# iprobe.net
KiCad netlist of a schematic drawn in EAGLE
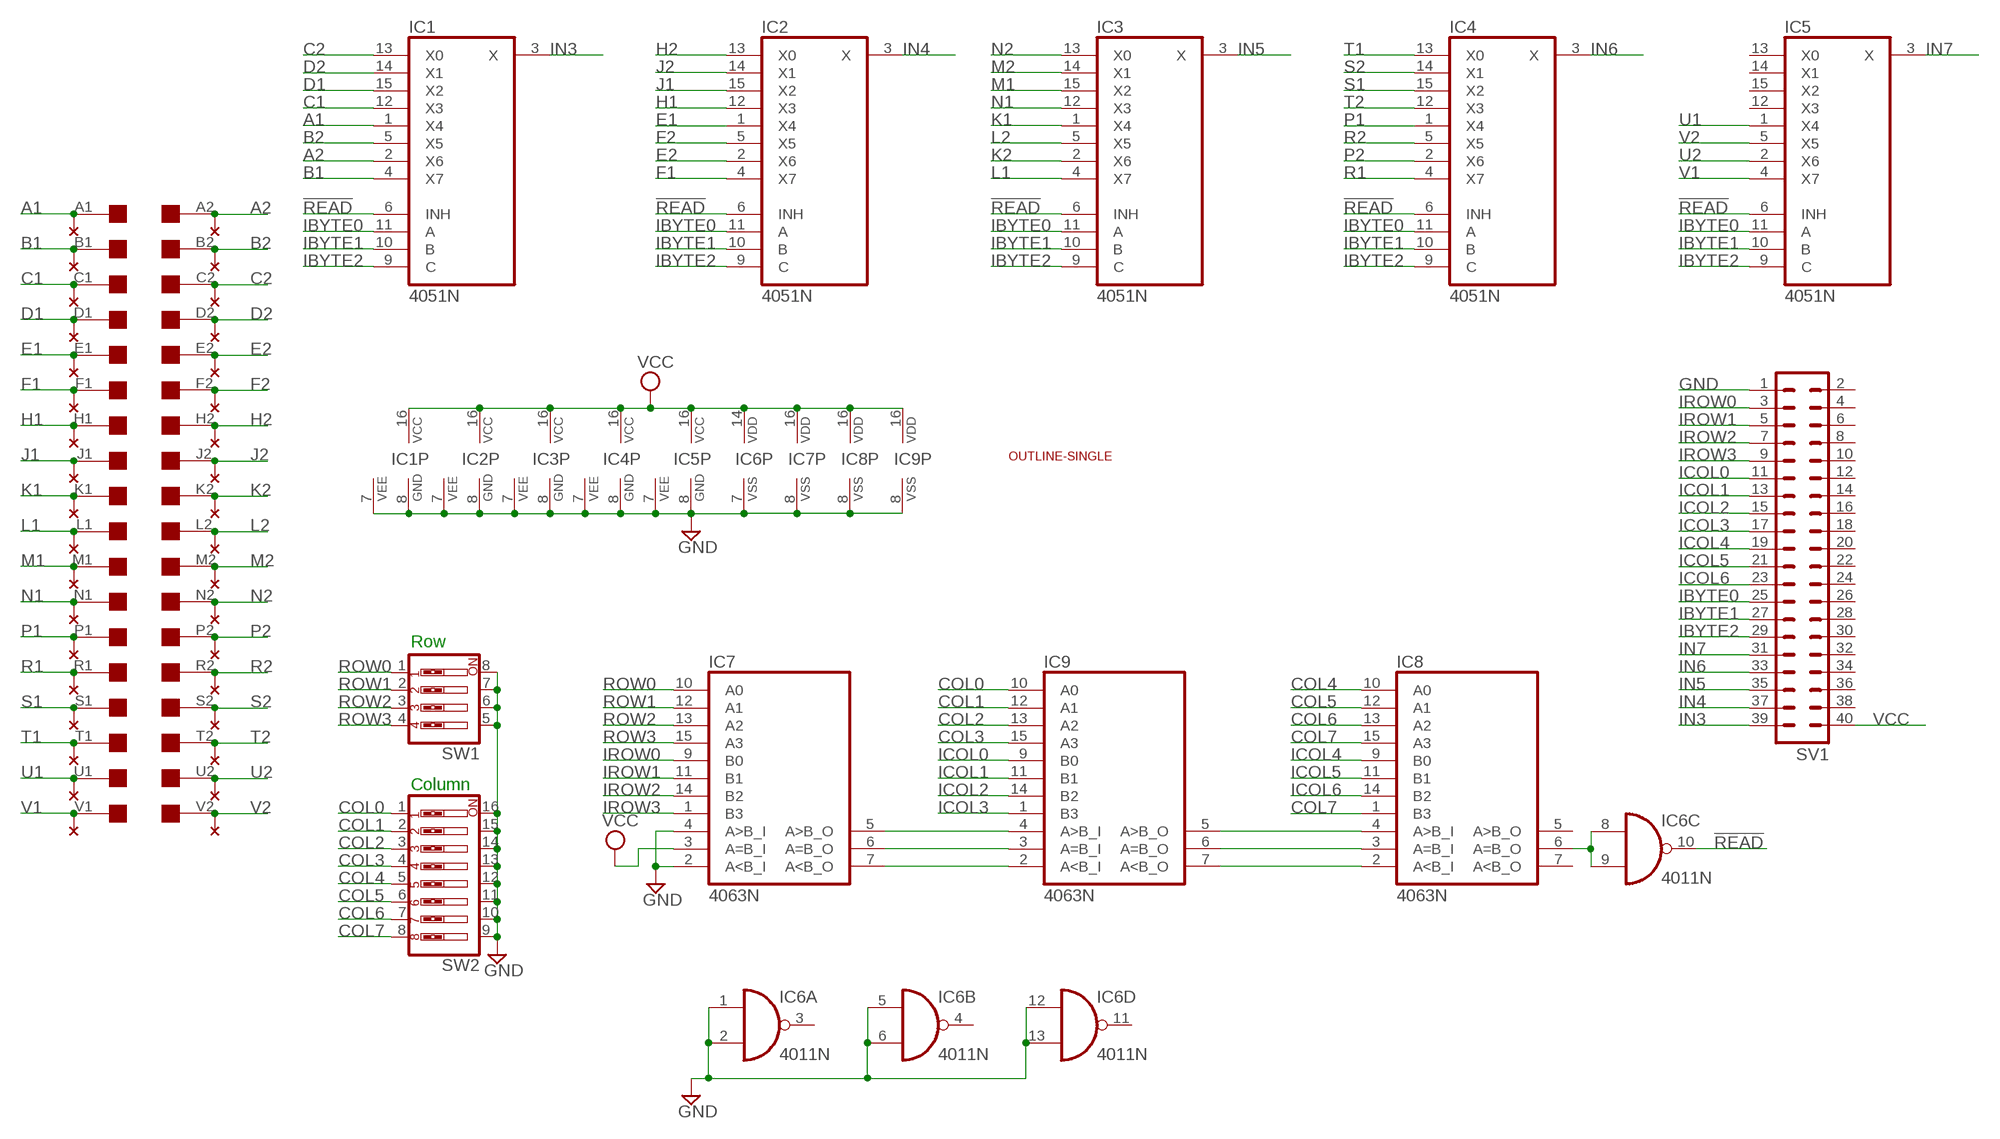
[diagram p0: schematic, sheet 1]

(export (version "E")
  (design (tool "Eeschema 10.0.6"))
  (components
    (comp (ref "EDGE1")
      (value "EDGE-2CONNECTOR")
      (footprint "eagle-import:EDGE-CON2")
      (libsource (lib "eagle-import") (part "EDGE-2CONNECTOR"))
    )
    (comp (ref "IC1")
      (value "4051N")
      (footprint "eagle-import:DIL16")
      (libsource (lib "eagle-import") (part "4051N"))
    )
    (comp (ref "IC2")
      (value "4051N")
      (footprint "eagle-import:DIL16")
      (libsource (lib "eagle-import") (part "4051N"))
    )
    (comp (ref "IC3")
      (value "4051N")
      (footprint "eagle-import:DIL16")
      (libsource (lib "eagle-import") (part "4051N"))
    )
    (comp (ref "IC4")
      (value "4051N")
      (footprint "eagle-import:DIL16")
      (libsource (lib "eagle-import") (part "4051N"))
    )
    (comp (ref "IC5")
      (value "4051N")
      (footprint "eagle-import:DIL16")
      (libsource (lib "eagle-import") (part "4051N"))
    )
    (comp (ref "IC6")
      (value "4011N")
      (footprint "eagle-import:DIL14")
      (libsource (lib "eagle-import") (part "4011N"))
    )
    (comp (ref "IC7")
      (value "4063N")
      (footprint "eagle-import:DIL16")
      (libsource (lib "eagle-import") (part "4063N"))
    )
    (comp (ref "IC8")
      (value "4063N")
      (footprint "eagle-import:DIL16")
      (libsource (lib "eagle-import") (part "4063N"))
    )
    (comp (ref "IC9")
      (value "4063N")
      (footprint "eagle-import:DIL16")
      (libsource (lib "eagle-import") (part "4063N"))
    )
    (comp (ref "SV1")
      (value "MA20-2")
      (footprint "eagle-import:MA20-2")
      (libsource (lib "eagle-import") (part "MA20-2"))
    )
    (comp (ref "SW1")
      (value "SW_DIP-4")
      (footprint "eagle-import:EDG-04")
      (libsource (lib "eagle-import") (part "SW_DIP-4"))
    )
    (comp (ref "SW2")
      (value "SW_DIP-8")
      (footprint "eagle-import:EDG-08")
      (libsource (lib "eagle-import") (part "SW_DIP-8"))
    )
    (comp (ref "U$2")
      (value "THRU-HOLE2")
      (footprint "eagle-import:THRU-HOLEB")
      (libsource (lib "eagle-import") (part "THRU-HOLE2"))
    )
    (comp (ref "U$3")
      (value "OUTLINE-SINGLE")
      (footprint "eagle-import:SINGLE")
      (libsource (lib "eagle-import") (part "OUTLINE-SINGLE"))
    )
  )
  (nets
    (net (code "1") (name "/A1") (class "Default")
      (node (ref "EDGE1") (pin "A1") (pinfunction "1_A1") (pintype "bidirectional"))
      (node (ref "IC1") (pin "1") (pinfunction "X4_1") (pintype "bidirectional"))
      (node (ref "U$2") (pin "A1") (pinfunction "P$1_A1") (pintype "passive"))
    )
    (net (code "2") (name "/A2") (class "Default")
      (node (ref "EDGE1") (pin "A2") (pinfunction "1_A2") (pintype "bidirectional"))
      (node (ref "IC1") (pin "2") (pinfunction "X6_2") (pintype "bidirectional"))
      (node (ref "U$2") (pin "A2") (pinfunction "P$1_A2") (pintype "passive"))
    )
    (net (code "3") (name "/B1") (class "Default")
      (node (ref "EDGE1") (pin "B1") (pinfunction "1_B1") (pintype "bidirectional"))
      (node (ref "IC1") (pin "4") (pinfunction "X7_4") (pintype "bidirectional"))
      (node (ref "U$2") (pin "B1") (pinfunction "P$1_B1") (pintype "passive"))
    )
    (net (code "4") (name "/B2") (class "Default")
      (node (ref "EDGE1") (pin "B2") (pinfunction "1_B2") (pintype "bidirectional"))
      (node (ref "IC1") (pin "5") (pinfunction "X5_5") (pintype "bidirectional"))
      (node (ref "U$2") (pin "B2") (pinfunction "P$1_B2") (pintype "passive"))
    )
    (net (code "5") (name "/C1") (class "Default")
      (node (ref "EDGE1") (pin "C1") (pinfunction "1_C1") (pintype "bidirectional"))
      (node (ref "IC1") (pin "12") (pinfunction "X3_12") (pintype "bidirectional"))
      (node (ref "U$2") (pin "C1") (pinfunction "P$1_C1") (pintype "passive"))
    )
    (net (code "6") (name "/C2") (class "Default")
      (node (ref "EDGE1") (pin "C2") (pinfunction "1_C2") (pintype "bidirectional"))
      (node (ref "IC1") (pin "13") (pinfunction "X0_13") (pintype "bidirectional"))
      (node (ref "U$2") (pin "C2") (pinfunction "P$1_C2") (pintype "passive"))
    )
    (net (code "7") (name "/COL0") (class "Default")
      (node (ref "IC9") (pin "10") (pinfunction "A0_10") (pintype "input"))
      (node (ref "SW2") (pin "1") (pinfunction "1_1") (pintype "passive"))
    )
    (net (code "8") (name "/COL1") (class "Default")
      (node (ref "IC9") (pin "12") (pinfunction "A1_12") (pintype "input"))
      (node (ref "SW2") (pin "2") (pinfunction "2_2") (pintype "passive"))
    )
    (net (code "9") (name "/COL2") (class "Default")
      (node (ref "IC9") (pin "13") (pinfunction "A2_13") (pintype "input"))
      (node (ref "SW2") (pin "3") (pinfunction "3_3") (pintype "passive"))
    )
    (net (code "10") (name "/COL3") (class "Default")
      (node (ref "IC9") (pin "15") (pinfunction "A3_15") (pintype "input"))
      (node (ref "SW2") (pin "4") (pinfunction "4_4") (pintype "passive"))
    )
    (net (code "11") (name "/COL4") (class "Default")
      (node (ref "IC8") (pin "10") (pinfunction "A0_10") (pintype "input"))
      (node (ref "SW2") (pin "5") (pinfunction "5_5") (pintype "passive"))
    )
    (net (code "12") (name "/COL5") (class "Default")
      (node (ref "IC8") (pin "12") (pinfunction "A1_12") (pintype "input"))
      (node (ref "SW2") (pin "6") (pinfunction "6_6") (pintype "passive"))
    )
    (net (code "13") (name "/COL6") (class "Default")
      (node (ref "IC8") (pin "13") (pinfunction "A2_13") (pintype "input"))
      (node (ref "SW2") (pin "7") (pinfunction "7_7") (pintype "passive"))
    )
    (net (code "14") (name "/COL7") (class "Default")
      (node (ref "IC8") (pin "1") (pinfunction "B3_1") (pintype "input"))
      (node (ref "IC8") (pin "15") (pinfunction "A3_15") (pintype "input"))
      (node (ref "SW2") (pin "8") (pinfunction "8_8") (pintype "passive"))
    )
    (net (code "15") (name "/D1") (class "Default")
      (node (ref "EDGE1") (pin "D1") (pinfunction "1_D1") (pintype "bidirectional"))
      (node (ref "IC1") (pin "15") (pinfunction "X2_15") (pintype "bidirectional"))
      (node (ref "U$2") (pin "D1") (pinfunction "P$1_D1") (pintype "passive"))
    )
    (net (code "16") (name "/D2") (class "Default")
      (node (ref "EDGE1") (pin "D2") (pinfunction "1_D2") (pintype "bidirectional"))
      (node (ref "IC1") (pin "14") (pinfunction "X1_14") (pintype "bidirectional"))
      (node (ref "U$2") (pin "D2") (pinfunction "P$1_D2") (pintype "passive"))
    )
    (net (code "17") (name "/E1") (class "Default")
      (node (ref "EDGE1") (pin "E1") (pinfunction "1_E1") (pintype "bidirectional"))
      (node (ref "IC2") (pin "1") (pinfunction "X4_1") (pintype "bidirectional"))
      (node (ref "U$2") (pin "E1") (pinfunction "P$1_E1") (pintype "passive"))
    )
    (net (code "18") (name "/E2") (class "Default")
      (node (ref "EDGE1") (pin "E2") (pinfunction "1_E2") (pintype "bidirectional"))
      (node (ref "IC2") (pin "2") (pinfunction "X6_2") (pintype "bidirectional"))
      (node (ref "U$2") (pin "E2") (pinfunction "P$1_E2") (pintype "passive"))
    )
    (net (code "19") (name "/F1") (class "Default")
      (node (ref "EDGE1") (pin "F1") (pinfunction "1_F1") (pintype "bidirectional"))
      (node (ref "IC2") (pin "4") (pinfunction "X7_4") (pintype "bidirectional"))
      (node (ref "U$2") (pin "F1") (pinfunction "P$1_F1") (pintype "passive"))
    )
    (net (code "20") (name "/F2") (class "Default")
      (node (ref "EDGE1") (pin "F2") (pinfunction "1_F2") (pintype "bidirectional"))
      (node (ref "IC2") (pin "5") (pinfunction "X5_5") (pintype "bidirectional"))
      (node (ref "U$2") (pin "F2") (pinfunction "P$1_F2") (pintype "passive"))
    )
    (net (code "21") (name "/H1") (class "Default")
      (node (ref "EDGE1") (pin "H1") (pinfunction "1_H1") (pintype "bidirectional"))
      (node (ref "IC2") (pin "12") (pinfunction "X3_12") (pintype "bidirectional"))
      (node (ref "U$2") (pin "H1") (pinfunction "P$1_H1") (pintype "passive"))
    )
    (net (code "22") (name "/H2") (class "Default")
      (node (ref "EDGE1") (pin "H2") (pinfunction "1_H2") (pintype "bidirectional"))
      (node (ref "IC2") (pin "13") (pinfunction "X0_13") (pintype "bidirectional"))
      (node (ref "U$2") (pin "H2") (pinfunction "P$1_H2") (pintype "passive"))
    )
    (net (code "23") (name "/IBYTE0") (class "Default")
      (node (ref "IC1") (pin "11") (pinfunction "A_11") (pintype "input"))
      (node (ref "IC2") (pin "11") (pinfunction "A_11") (pintype "input"))
      (node (ref "IC3") (pin "11") (pinfunction "A_11") (pintype "input"))
      (node (ref "IC4") (pin "11") (pinfunction "A_11") (pintype "input"))
      (node (ref "IC5") (pin "11") (pinfunction "A_11") (pintype "input"))
      (node (ref "SV1") (pin "25") (pinfunction "25_25") (pintype "passive"))
    )
    (net (code "24") (name "/IBYTE1") (class "Default")
      (node (ref "IC1") (pin "10") (pinfunction "B_10") (pintype "input"))
      (node (ref "IC2") (pin "10") (pinfunction "B_10") (pintype "input"))
      (node (ref "IC3") (pin "10") (pinfunction "B_10") (pintype "input"))
      (node (ref "IC4") (pin "10") (pinfunction "B_10") (pintype "input"))
      (node (ref "IC5") (pin "10") (pinfunction "B_10") (pintype "input"))
      (node (ref "SV1") (pin "27") (pinfunction "27_27") (pintype "passive"))
    )
    (net (code "25") (name "/IBYTE2") (class "Default")
      (node (ref "IC1") (pin "9") (pinfunction "C_9") (pintype "input"))
      (node (ref "IC2") (pin "9") (pinfunction "C_9") (pintype "input"))
      (node (ref "IC3") (pin "9") (pinfunction "C_9") (pintype "input"))
      (node (ref "IC4") (pin "9") (pinfunction "C_9") (pintype "input"))
      (node (ref "IC5") (pin "9") (pinfunction "C_9") (pintype "input"))
      (node (ref "SV1") (pin "29") (pinfunction "29_29") (pintype "passive"))
    )
    (net (code "26") (name "/ICOL0") (class "Default")
      (node (ref "IC9") (pin "9") (pinfunction "B0_9") (pintype "input"))
      (node (ref "SV1") (pin "11") (pinfunction "11_11") (pintype "passive"))
    )
    (net (code "27") (name "/ICOL1") (class "Default")
      (node (ref "IC9") (pin "11") (pinfunction "B1_11") (pintype "input"))
      (node (ref "SV1") (pin "13") (pinfunction "13_13") (pintype "passive"))
    )
    (net (code "28") (name "/ICOL2") (class "Default")
      (node (ref "IC9") (pin "14") (pinfunction "B2_14") (pintype "input"))
      (node (ref "SV1") (pin "15") (pinfunction "15_15") (pintype "passive"))
    )
    (net (code "29") (name "/ICOL3") (class "Default")
      (node (ref "IC9") (pin "1") (pinfunction "B3_1") (pintype "input"))
      (node (ref "SV1") (pin "17") (pinfunction "17_17") (pintype "passive"))
    )
    (net (code "30") (name "/ICOL4") (class "Default")
      (node (ref "IC8") (pin "9") (pinfunction "B0_9") (pintype "input"))
      (node (ref "SV1") (pin "19") (pinfunction "19_19") (pintype "passive"))
    )
    (net (code "31") (name "/ICOL5") (class "Default")
      (node (ref "IC8") (pin "11") (pinfunction "B1_11") (pintype "input"))
      (node (ref "SV1") (pin "21") (pinfunction "21_21") (pintype "passive"))
    )
    (net (code "32") (name "/ICOL6") (class "Default")
      (node (ref "IC8") (pin "14") (pinfunction "B2_14") (pintype "input"))
      (node (ref "SV1") (pin "23") (pinfunction "23_23") (pintype "passive"))
    )
    (net (code "33") (name "/IN3") (class "Default")
      (node (ref "IC1") (pin "3") (pinfunction "X_3") (pintype "bidirectional"))
      (node (ref "SV1") (pin "39") (pinfunction "39_39") (pintype "passive"))
    )
    (net (code "34") (name "/IN4") (class "Default")
      (node (ref "IC2") (pin "3") (pinfunction "X_3") (pintype "bidirectional"))
      (node (ref "SV1") (pin "37") (pinfunction "37_37") (pintype "passive"))
    )
    (net (code "35") (name "/IN5") (class "Default")
      (node (ref "IC3") (pin "3") (pinfunction "X_3") (pintype "bidirectional"))
      (node (ref "SV1") (pin "35") (pinfunction "35_35") (pintype "passive"))
    )
    (net (code "36") (name "/IN6") (class "Default")
      (node (ref "IC4") (pin "3") (pinfunction "X_3") (pintype "bidirectional"))
      (node (ref "SV1") (pin "33") (pinfunction "33_33") (pintype "passive"))
    )
    (net (code "37") (name "/IN7") (class "Default")
      (node (ref "IC5") (pin "3") (pinfunction "X_3") (pintype "bidirectional"))
      (node (ref "SV1") (pin "31") (pinfunction "31_31") (pintype "passive"))
    )
    (net (code "38") (name "/IROW0") (class "Default")
      (node (ref "IC7") (pin "9") (pinfunction "B0_9") (pintype "input"))
      (node (ref "SV1") (pin "3") (pinfunction "3_3") (pintype "passive"))
    )
    (net (code "39") (name "/IROW1") (class "Default")
      (node (ref "IC7") (pin "11") (pinfunction "B1_11") (pintype "input"))
      (node (ref "SV1") (pin "5") (pinfunction "5_5") (pintype "passive"))
    )
    (net (code "40") (name "/IROW2") (class "Default")
      (node (ref "IC7") (pin "14") (pinfunction "B2_14") (pintype "input"))
      (node (ref "SV1") (pin "7") (pinfunction "7_7") (pintype "passive"))
    )
    (net (code "41") (name "/IROW3") (class "Default")
      (node (ref "IC7") (pin "1") (pinfunction "B3_1") (pintype "input"))
      (node (ref "SV1") (pin "9") (pinfunction "9_9") (pintype "passive"))
    )
    (net (code "42") (name "/J1") (class "Default")
      (node (ref "EDGE1") (pin "J1") (pinfunction "1_J1") (pintype "bidirectional"))
      (node (ref "IC2") (pin "15") (pinfunction "X2_15") (pintype "bidirectional"))
      (node (ref "U$2") (pin "J1") (pinfunction "P$1_J1") (pintype "passive"))
    )
    (net (code "43") (name "/J2") (class "Default")
      (node (ref "EDGE1") (pin "J2") (pinfunction "1_J2") (pintype "bidirectional"))
      (node (ref "IC2") (pin "14") (pinfunction "X1_14") (pintype "bidirectional"))
      (node (ref "U$2") (pin "J2") (pinfunction "P$1_J2") (pintype "passive"))
    )
    (net (code "44") (name "/K1") (class "Default")
      (node (ref "EDGE1") (pin "K1") (pinfunction "1_K1") (pintype "bidirectional"))
      (node (ref "IC3") (pin "1") (pinfunction "X4_1") (pintype "bidirectional"))
      (node (ref "U$2") (pin "K1") (pinfunction "P$1_K1") (pintype "passive"))
    )
    (net (code "45") (name "/K2") (class "Default")
      (node (ref "EDGE1") (pin "K2") (pinfunction "1_K2") (pintype "bidirectional"))
      (node (ref "IC3") (pin "2") (pinfunction "X6_2") (pintype "bidirectional"))
      (node (ref "U$2") (pin "K2") (pinfunction "P$1_K2") (pintype "passive"))
    )
    (net (code "46") (name "/L1") (class "Default")
      (node (ref "EDGE1") (pin "L1") (pinfunction "1_L1") (pintype "bidirectional"))
      (node (ref "IC3") (pin "4") (pinfunction "X7_4") (pintype "bidirectional"))
      (node (ref "U$2") (pin "L1") (pinfunction "P$1_L1") (pintype "passive"))
    )
    (net (code "47") (name "/L2") (class "Default")
      (node (ref "EDGE1") (pin "L2") (pinfunction "1_L2") (pintype "bidirectional"))
      (node (ref "IC3") (pin "5") (pinfunction "X5_5") (pintype "bidirectional"))
      (node (ref "U$2") (pin "L2") (pinfunction "P$1_L2") (pintype "passive"))
    )
    (net (code "48") (name "/M1") (class "Default")
      (node (ref "EDGE1") (pin "M1") (pinfunction "1_M1") (pintype "bidirectional"))
      (node (ref "IC3") (pin "15") (pinfunction "X2_15") (pintype "bidirectional"))
      (node (ref "U$2") (pin "M1") (pinfunction "P$1_M1") (pintype "passive"))
    )
    (net (code "49") (name "/M2") (class "Default")
      (node (ref "EDGE1") (pin "M2") (pinfunction "1_M2") (pintype "bidirectional"))
      (node (ref "IC3") (pin "14") (pinfunction "X1_14") (pintype "bidirectional"))
      (node (ref "U$2") (pin "M2") (pinfunction "P$1_M2") (pintype "passive"))
    )
    (net (code "50") (name "/N1") (class "Default")
      (node (ref "EDGE1") (pin "N1") (pinfunction "1_N1") (pintype "bidirectional"))
      (node (ref "IC3") (pin "12") (pinfunction "X3_12") (pintype "bidirectional"))
      (node (ref "U$2") (pin "N1") (pinfunction "P$1_N1") (pintype "passive"))
    )
    (net (code "51") (name "/N2") (class "Default")
      (node (ref "EDGE1") (pin "N2") (pinfunction "1_N2") (pintype "bidirectional"))
      (node (ref "IC3") (pin "13") (pinfunction "X0_13") (pintype "bidirectional"))
      (node (ref "U$2") (pin "N2") (pinfunction "P$1_N2") (pintype "passive"))
    )
    (net (code "52") (name "/P1") (class "Default")
      (node (ref "EDGE1") (pin "P1") (pinfunction "1_P1") (pintype "bidirectional"))
      (node (ref "IC4") (pin "1") (pinfunction "X4_1") (pintype "bidirectional"))
      (node (ref "U$2") (pin "P1") (pinfunction "P$1_P1") (pintype "passive"))
    )
    (net (code "53") (name "/P2") (class "Default")
      (node (ref "EDGE1") (pin "P2") (pinfunction "1_P2") (pintype "bidirectional"))
      (node (ref "IC4") (pin "2") (pinfunction "X6_2") (pintype "bidirectional"))
      (node (ref "U$2") (pin "P2") (pinfunction "P$1_P2") (pintype "passive"))
    )
    (net (code "54") (name "/R1") (class "Default")
      (node (ref "EDGE1") (pin "R1") (pinfunction "1_R1") (pintype "bidirectional"))
      (node (ref "IC4") (pin "4") (pinfunction "X7_4") (pintype "bidirectional"))
      (node (ref "U$2") (pin "R1") (pinfunction "P$1_R1") (pintype "passive"))
    )
    (net (code "55") (name "/R2") (class "Default")
      (node (ref "EDGE1") (pin "R2") (pinfunction "1_R2") (pintype "bidirectional"))
      (node (ref "IC4") (pin "5") (pinfunction "X5_5") (pintype "bidirectional"))
      (node (ref "U$2") (pin "R2") (pinfunction "P$1_R2") (pintype "passive"))
    )
    (net (code "56") (name "/ROW0") (class "Default")
      (node (ref "IC7") (pin "10") (pinfunction "A0_10") (pintype "input"))
      (node (ref "SW1") (pin "1") (pinfunction "1_1") (pintype "passive"))
    )
    (net (code "57") (name "/ROW1") (class "Default")
      (node (ref "IC7") (pin "12") (pinfunction "A1_12") (pintype "input"))
      (node (ref "SW1") (pin "2") (pinfunction "2_2") (pintype "passive"))
    )
    (net (code "58") (name "/ROW2") (class "Default")
      (node (ref "IC7") (pin "13") (pinfunction "A2_13") (pintype "input"))
      (node (ref "SW1") (pin "3") (pinfunction "3_3") (pintype "passive"))
    )
    (net (code "59") (name "/ROW3") (class "Default")
      (node (ref "IC7") (pin "15") (pinfunction "A3_15") (pintype "input"))
      (node (ref "SW1") (pin "4") (pinfunction "4_4") (pintype "passive"))
    )
    (net (code "60") (name "/S1") (class "Default")
      (node (ref "EDGE1") (pin "S1") (pinfunction "1_S1") (pintype "bidirectional"))
      (node (ref "IC4") (pin "15") (pinfunction "X2_15") (pintype "bidirectional"))
      (node (ref "U$2") (pin "S1") (pinfunction "P$1_S1") (pintype "passive"))
    )
    (net (code "61") (name "/S2") (class "Default")
      (node (ref "EDGE1") (pin "S2") (pinfunction "1_S2") (pintype "bidirectional"))
      (node (ref "IC4") (pin "14") (pinfunction "X1_14") (pintype "bidirectional"))
      (node (ref "U$2") (pin "S2") (pinfunction "P$1_S2") (pintype "passive"))
    )
    (net (code "62") (name "/T1") (class "Default")
      (node (ref "EDGE1") (pin "T1") (pinfunction "1_T1") (pintype "bidirectional"))
      (node (ref "IC4") (pin "13") (pinfunction "X0_13") (pintype "bidirectional"))
      (node (ref "U$2") (pin "T1") (pinfunction "P$1_T1") (pintype "passive"))
    )
    (net (code "63") (name "/T2") (class "Default")
      (node (ref "EDGE1") (pin "T2") (pinfunction "1_T2") (pintype "bidirectional"))
      (node (ref "IC4") (pin "12") (pinfunction "X3_12") (pintype "bidirectional"))
      (node (ref "U$2") (pin "T2") (pinfunction "P$1_T2") (pintype "passive"))
    )
    (net (code "64") (name "/U1") (class "Default")
      (node (ref "EDGE1") (pin "U1") (pinfunction "1_U1") (pintype "bidirectional"))
      (node (ref "IC5") (pin "1") (pinfunction "X4_1") (pintype "bidirectional"))
      (node (ref "U$2") (pin "U1") (pinfunction "P$1_U1") (pintype "passive"))
    )
    (net (code "65") (name "/U2") (class "Default")
      (node (ref "EDGE1") (pin "U2") (pinfunction "1_U2") (pintype "bidirectional"))
      (node (ref "IC5") (pin "2") (pinfunction "X6_2") (pintype "bidirectional"))
      (node (ref "U$2") (pin "U2") (pinfunction "P$1_U2") (pintype "passive"))
    )
    (net (code "66") (name "/V1") (class "Default")
      (node (ref "EDGE1") (pin "V1") (pinfunction "1_V1") (pintype "bidirectional"))
      (node (ref "IC5") (pin "4") (pinfunction "X7_4") (pintype "bidirectional"))
      (node (ref "U$2") (pin "V1") (pinfunction "P$1_V1") (pintype "passive"))
    )
    (net (code "67") (name "/V2") (class "Default")
      (node (ref "EDGE1") (pin "V2") (pinfunction "1_V2") (pintype "bidirectional"))
      (node (ref "IC5") (pin "5") (pinfunction "X5_5") (pintype "bidirectional"))
      (node (ref "U$2") (pin "V2") (pinfunction "P$1_V2") (pintype "passive"))
    )
    (net (code "68") (name "/~{READ}") (class "Default")
      (node (ref "IC1") (pin "6") (pinfunction "INH_6") (pintype "input"))
      (node (ref "IC2") (pin "6") (pinfunction "INH_6") (pintype "input"))
      (node (ref "IC3") (pin "6") (pinfunction "INH_6") (pintype "input"))
      (node (ref "IC4") (pin "6") (pinfunction "INH_6") (pintype "input"))
      (node (ref "IC5") (pin "6") (pinfunction "INH_6") (pintype "input"))
      (node (ref "IC6") (pin "10") (pinfunction "O_10") (pintype "output"))
    )
    (net (code "69") (name "GND") (class "Default")
      (node (ref "IC1") (pin "7") (pinfunction "VEE_7") (pintype "power_in"))
      (node (ref "IC1") (pin "8") (pinfunction "GND_8") (pintype "power_in"))
      (node (ref "IC2") (pin "7") (pinfunction "VEE_7") (pintype "power_in"))
      (node (ref "IC2") (pin "8") (pinfunction "GND_8") (pintype "power_in"))
      (node (ref "IC3") (pin "7") (pinfunction "VEE_7") (pintype "power_in"))
      (node (ref "IC3") (pin "8") (pinfunction "GND_8") (pintype "power_in"))
      (node (ref "IC4") (pin "7") (pinfunction "VEE_7") (pintype "power_in"))
      (node (ref "IC4") (pin "8") (pinfunction "GND_8") (pintype "power_in"))
      (node (ref "IC5") (pin "7") (pinfunction "VEE_7") (pintype "power_in"))
      (node (ref "IC5") (pin "8") (pinfunction "GND_8") (pintype "power_in"))
      (node (ref "IC6") (pin "1") (pinfunction "I0_1") (pintype "input"))
      (node (ref "IC6") (pin "12") (pinfunction "I0_12") (pintype "input"))
      (node (ref "IC6") (pin "13") (pinfunction "I1_13") (pintype "input"))
      (node (ref "IC6") (pin "2") (pinfunction "I1_2") (pintype "input"))
      (node (ref "IC6") (pin "5") (pinfunction "I0_5") (pintype "input"))
      (node (ref "IC6") (pin "6") (pinfunction "I1_6") (pintype "input"))
      (node (ref "IC6") (pin "7") (pinfunction "VSS_7") (pintype "power_in"))
      (node (ref "IC7") (pin "2") (pinfunction "A<B_I_2") (pintype "input"))
      (node (ref "IC7") (pin "4") (pinfunction "A>B_I_4") (pintype "input"))
      (node (ref "IC7") (pin "8") (pinfunction "VSS_8") (pintype "power_in"))
      (node (ref "IC8") (pin "8") (pinfunction "VSS_8") (pintype "power_in"))
      (node (ref "IC9") (pin "8") (pinfunction "VSS_8") (pintype "power_in"))
      (node (ref "SV1") (pin "1") (pinfunction "1_1") (pintype "passive"))
      (node (ref "SW1") (pin "5") (pinfunction "5_5") (pintype "passive"))
      (node (ref "SW1") (pin "6") (pinfunction "6_6") (pintype "passive"))
      (node (ref "SW1") (pin "7") (pinfunction "7_7") (pintype "passive"))
      (node (ref "SW1") (pin "8") (pinfunction "8_8") (pintype "passive"))
      (node (ref "SW2") (pin "10") (pinfunction "10_10") (pintype "passive"))
      (node (ref "SW2") (pin "11") (pinfunction "11_11") (pintype "passive"))
      (node (ref "SW2") (pin "12") (pinfunction "12_12") (pintype "passive"))
      (node (ref "SW2") (pin "13") (pinfunction "13_13") (pintype "passive"))
      (node (ref "SW2") (pin "14") (pinfunction "14_14") (pintype "passive"))
      (node (ref "SW2") (pin "15") (pinfunction "15_15") (pintype "passive"))
      (node (ref "SW2") (pin "16") (pinfunction "16_16") (pintype "passive"))
      (node (ref "SW2") (pin "9") (pinfunction "9_9") (pintype "passive"))
    )
    (net (code "70") (name "Net-(IC6C-I0)") (class "Default")
      (node (ref "IC6") (pin "8") (pinfunction "I0_8") (pintype "input"))
      (node (ref "IC6") (pin "9") (pinfunction "I1_9") (pintype "input"))
      (node (ref "IC8") (pin "6") (pinfunction "A=B_O_6") (pintype "output"))
    )
    (net (code "71") (name "Net-(IC7A-A<B_O)") (class "Default")
      (node (ref "IC7") (pin "7") (pinfunction "A<B_O_7") (pintype "output"))
      (node (ref "IC9") (pin "2") (pinfunction "A<B_I_2") (pintype "input"))
    )
    (net (code "72") (name "Net-(IC7A-A=B_O)") (class "Default")
      (node (ref "IC7") (pin "6") (pinfunction "A=B_O_6") (pintype "output"))
      (node (ref "IC9") (pin "3") (pinfunction "A=B_I_3") (pintype "input"))
    )
    (net (code "73") (name "Net-(IC7A-A>B_O)") (class "Default")
      (node (ref "IC7") (pin "5") (pinfunction "A>B_O_5") (pintype "output"))
      (node (ref "IC9") (pin "4") (pinfunction "A>B_I_4") (pintype "input"))
    )
    (net (code "74") (name "Net-(IC8A-A<B_I)") (class "Default")
      (node (ref "IC8") (pin "2") (pinfunction "A<B_I_2") (pintype "input"))
      (node (ref "IC9") (pin "7") (pinfunction "A<B_O_7") (pintype "output"))
    )
    (net (code "75") (name "Net-(IC8A-A=B_I)") (class "Default")
      (node (ref "IC8") (pin "3") (pinfunction "A=B_I_3") (pintype "input"))
      (node (ref "IC9") (pin "6") (pinfunction "A=B_O_6") (pintype "output"))
    )
    (net (code "76") (name "Net-(IC8A-A>B_I)") (class "Default")
      (node (ref "IC8") (pin "4") (pinfunction "A>B_I_4") (pintype "input"))
      (node (ref "IC9") (pin "5") (pinfunction "A>B_O_5") (pintype "output"))
    )
    (net (code "77") (name "VCC") (class "Default")
      (node (ref "IC1") (pin "16") (pinfunction "VCC_16") (pintype "power_in"))
      (node (ref "IC2") (pin "16") (pinfunction "VCC_16") (pintype "power_in"))
      (node (ref "IC3") (pin "16") (pinfunction "VCC_16") (pintype "power_in"))
      (node (ref "IC4") (pin "16") (pinfunction "VCC_16") (pintype "power_in"))
      (node (ref "IC5") (pin "16") (pinfunction "VCC_16") (pintype "power_in"))
      (node (ref "IC6") (pin "14") (pinfunction "VDD_14") (pintype "power_in"))
      (node (ref "IC7") (pin "16") (pinfunction "VDD_16") (pintype "power_in"))
      (node (ref "IC7") (pin "3") (pinfunction "A=B_I_3") (pintype "input"))
      (node (ref "IC8") (pin "16") (pinfunction "VDD_16") (pintype "power_in"))
      (node (ref "IC9") (pin "16") (pinfunction "VDD_16") (pintype "power_in"))
      (node (ref "SV1") (pin "40") (pinfunction "40_40") (pintype "passive"))
    )
    (net (code "78") (name "unconnected-(IC5A-X0-Pad13)") (class "Default")
      (node (ref "IC5") (pin "13") (pinfunction "X0_13") (pintype "bidirectional"))
    )
    (net (code "79") (name "unconnected-(IC5A-X1-Pad14)") (class "Default")
      (node (ref "IC5") (pin "14") (pinfunction "X1_14") (pintype "bidirectional"))
    )
    (net (code "80") (name "unconnected-(IC5A-X2-Pad15)") (class "Default")
      (node (ref "IC5") (pin "15") (pinfunction "X2_15") (pintype "bidirectional"))
    )
    (net (code "81") (name "unconnected-(IC5A-X3-Pad12)") (class "Default")
      (node (ref "IC5") (pin "12") (pinfunction "X3_12") (pintype "bidirectional"))
    )
    (net (code "82") (name "unconnected-(IC6A-O-Pad3)") (class "Default")
      (node (ref "IC6") (pin "3") (pinfunction "O_3") (pintype "output"))
    )
    (net (code "83") (name "unconnected-(IC6B-O-Pad4)") (class "Default")
      (node (ref "IC6") (pin "4") (pinfunction "O_4") (pintype "output"))
    )
    (net (code "84") (name "unconnected-(IC6D-O-Pad11)") (class "Default")
      (node (ref "IC6") (pin "11") (pinfunction "O_11") (pintype "output"))
    )
    (net (code "85") (name "unconnected-(IC8A-A<B_O-Pad7)") (class "Default")
      (node (ref "IC8") (pin "7") (pinfunction "A<B_O_7") (pintype "output"))
    )
    (net (code "86") (name "unconnected-(IC8A-A>B_O-Pad5)") (class "Default")
      (node (ref "IC8") (pin "5") (pinfunction "A>B_O_5") (pintype "output"))
    )
    (net (code "87") (name "unconnected-(SV1-Pad2)") (class "Default")
      (node (ref "SV1") (pin "2") (pinfunction "2_2") (pintype "passive"))
    )
    (net (code "88") (name "unconnected-(SV1-Pad4)") (class "Default")
      (node (ref "SV1") (pin "4") (pinfunction "4_4") (pintype "passive"))
    )
    (net (code "89") (name "unconnected-(SV1-Pad6)") (class "Default")
      (node (ref "SV1") (pin "6") (pinfunction "6_6") (pintype "passive"))
    )
    (net (code "90") (name "unconnected-(SV1-Pad8)") (class "Default")
      (node (ref "SV1") (pin "8") (pinfunction "8_8") (pintype "passive"))
    )
    (net (code "91") (name "unconnected-(SV1-Pad10)") (class "Default")
      (node (ref "SV1") (pin "10") (pinfunction "10_10") (pintype "passive"))
    )
    (net (code "92") (name "unconnected-(SV1-Pad12)") (class "Default")
      (node (ref "SV1") (pin "12") (pinfunction "12_12") (pintype "passive"))
    )
    (net (code "93") (name "unconnected-(SV1-Pad14)") (class "Default")
      (node (ref "SV1") (pin "14") (pinfunction "14_14") (pintype "passive"))
    )
    (net (code "94") (name "unconnected-(SV1-Pad16)") (class "Default")
      (node (ref "SV1") (pin "16") (pinfunction "16_16") (pintype "passive"))
    )
    (net (code "95") (name "unconnected-(SV1-Pad18)") (class "Default")
      (node (ref "SV1") (pin "18") (pinfunction "18_18") (pintype "passive"))
    )
    (net (code "96") (name "unconnected-(SV1-Pad20)") (class "Default")
      (node (ref "SV1") (pin "20") (pinfunction "20_20") (pintype "passive"))
    )
    (net (code "97") (name "unconnected-(SV1-Pad22)") (class "Default")
      (node (ref "SV1") (pin "22") (pinfunction "22_22") (pintype "passive"))
    )
    (net (code "98") (name "unconnected-(SV1-Pad24)") (class "Default")
      (node (ref "SV1") (pin "24") (pinfunction "24_24") (pintype "passive"))
    )
    (net (code "99") (name "unconnected-(SV1-Pad26)") (class "Default")
      (node (ref "SV1") (pin "26") (pinfunction "26_26") (pintype "passive"))
    )
    (net (code "100") (name "unconnected-(SV1-Pad28)") (class "Default")
      (node (ref "SV1") (pin "28") (pinfunction "28_28") (pintype "passive"))
    )
    (net (code "101") (name "unconnected-(SV1-Pad30)") (class "Default")
      (node (ref "SV1") (pin "30") (pinfunction "30_30") (pintype "passive"))
    )
    (net (code "102") (name "unconnected-(SV1-Pad32)") (class "Default")
      (node (ref "SV1") (pin "32") (pinfunction "32_32") (pintype "passive"))
    )
    (net (code "103") (name "unconnected-(SV1-Pad34)") (class "Default")
      (node (ref "SV1") (pin "34") (pinfunction "34_34") (pintype "passive"))
    )
    (net (code "104") (name "unconnected-(SV1-Pad36)") (class "Default")
      (node (ref "SV1") (pin "36") (pinfunction "36_36") (pintype "passive"))
    )
    (net (code "105") (name "unconnected-(SV1-Pad38)") (class "Default")
      (node (ref "SV1") (pin "38") (pinfunction "38_38") (pintype "passive"))
    )
  )
)
